# Dario_-_Rev_A2.net
KiCad netlist of a schematic drawn in EAGLE
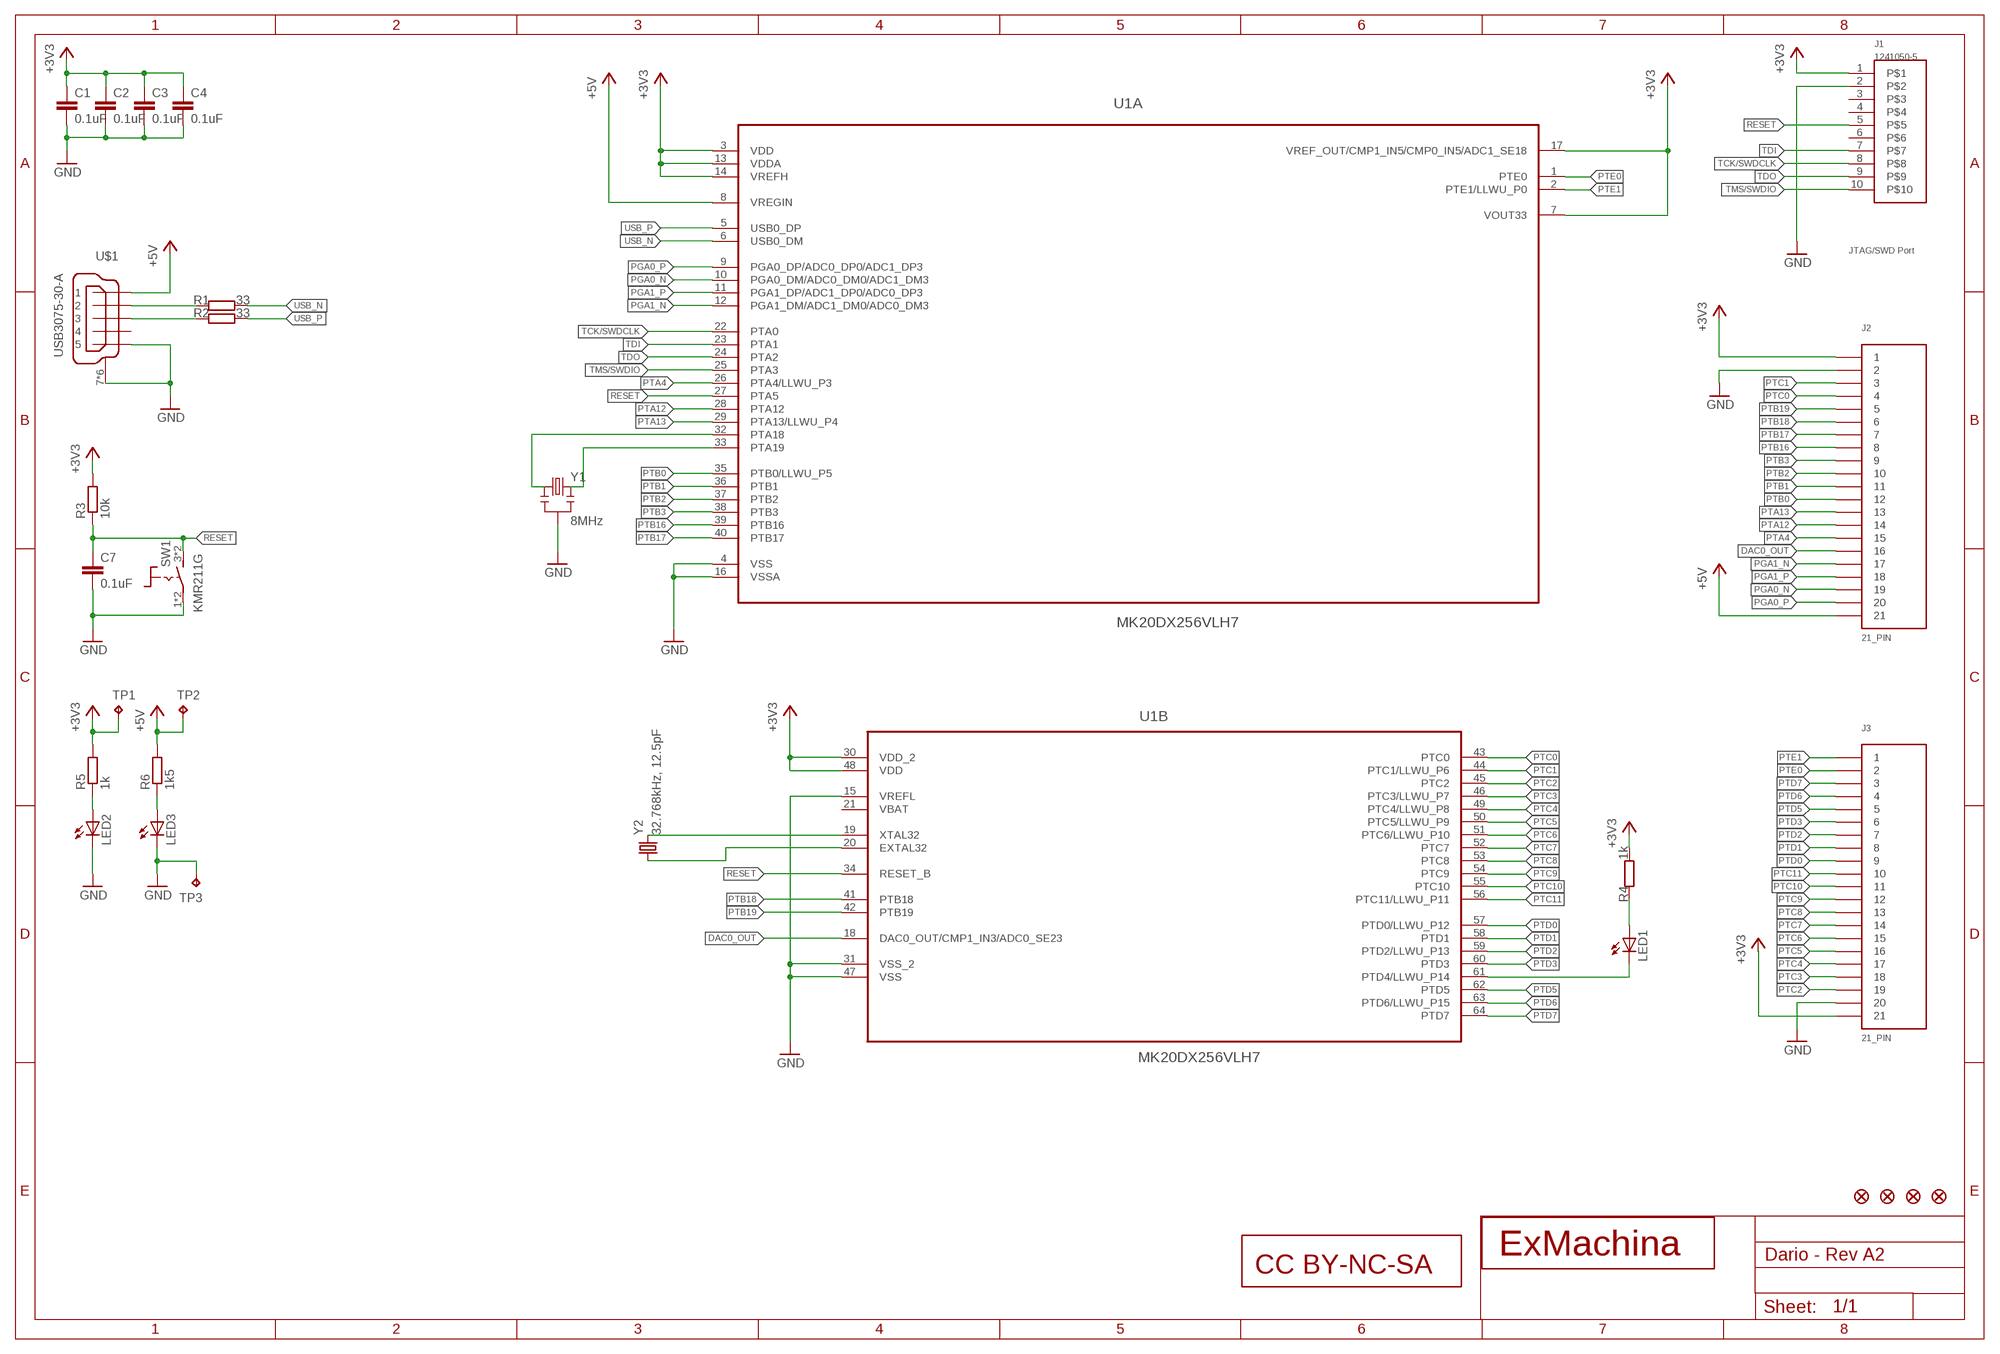
[diagram p0: schematic, sheet 1]

(export (version "E")
  (design (tool "Eeschema 10.0.6"))
  (components
    (comp (ref "C1")
      (value "0.1uF")
      (footprint "eagle-import:C0603")
      (fields (field (name "MPN") "MC0603B104K160CT"))
      (libsource (lib "eagle-import") (part "C-EUC0603"))
    )
    (comp (ref "C2")
      (value "0.1uF")
      (footprint "eagle-import:C0603")
      (fields (field (name "MPN") "MC0603B104K160CT"))
      (libsource (lib "eagle-import") (part "C-EUC0603"))
    )
    (comp (ref "C3")
      (value "0.1uF")
      (footprint "eagle-import:C0603")
      (fields (field (name "MPN") "MC0603B104K160CT"))
      (libsource (lib "eagle-import") (part "C-EUC0603"))
    )
    (comp (ref "C4")
      (value "0.1uF")
      (footprint "eagle-import:C0603")
      (fields (field (name "MPN") "MC0603B104K160CT"))
      (libsource (lib "eagle-import") (part "C-EUC0603"))
    )
    (comp (ref "C7")
      (value "0.1uF")
      (footprint "eagle-import:C0603")
      (fields (field (name "MPN") "MC0603B104K160CT"))
      (libsource (lib "eagle-import") (part "C-EUC0603"))
    )
    (comp (ref "J1")
      (value "1241050-5")
      (footprint "eagle-import:2.54_2X5")
      (libsource (lib "eagle-import") (part "1241050-5"))
    )
    (comp (ref "J2")
      (value "21_PIN")
      (footprint "eagle-import:21_CUSTOM")
      (libsource (lib "eagle-import") (part "21_PIN"))
    )
    (comp (ref "J3")
      (value "21_PIN")
      (footprint "eagle-import:21_CUSTOM")
      (libsource (lib "eagle-import") (part "21_PIN"))
    )
    (comp (ref "JP1")
      (value "FIDUCIAL1X2")
      (footprint "eagle-import:FIDUCIAL-1X2")
      (libsource (lib "eagle-import") (part "FIDUCIAL1X2"))
    )
    (comp (ref "JP2")
      (value "FIDUCIAL1X2")
      (footprint "eagle-import:FIDUCIAL-1X2")
      (libsource (lib "eagle-import") (part "FIDUCIAL1X2"))
    )
    (comp (ref "JP3")
      (value "FIDUCIAL1X2")
      (footprint "eagle-import:FIDUCIAL-1X2")
      (libsource (lib "eagle-import") (part "FIDUCIAL1X2"))
    )
    (comp (ref "JP4")
      (value "FIDUCIAL1X2")
      (footprint "eagle-import:FIDUCIAL-1X2")
      (libsource (lib "eagle-import") (part "FIDUCIAL1X2"))
    )
    (comp (ref "LED1")
      (value "LEDCHIP-LED0603")
      (footprint "eagle-import:CHIP-LED0603")
      (libsource (lib "eagle-import") (part "LEDCHIP-LED0603"))
    )
    (comp (ref "LED2")
      (value "LEDCHIP-LED0603")
      (footprint "eagle-import:CHIP-LED0603")
      (libsource (lib "eagle-import") (part "LEDCHIP-LED0603"))
    )
    (comp (ref "LED3")
      (value "LEDCHIP-LED0603")
      (footprint "eagle-import:CHIP-LED0603")
      (libsource (lib "eagle-import") (part "LEDCHIP-LED0603"))
    )
    (comp (ref "R1")
      (value "33")
      (footprint "eagle-import:R0603")
      (fields (field (name "MPN") "MCMR06X33R0FTL"))
      (libsource (lib "eagle-import") (part "R-EU_R0603"))
    )
    (comp (ref "R2")
      (value "33")
      (footprint "eagle-import:R0603")
      (fields (field (name "MPN") "MCMR06X33R0FTL"))
      (libsource (lib "eagle-import") (part "R-EU_R0603"))
    )
    (comp (ref "R3")
      (value "10k")
      (footprint "eagle-import:R0603")
      (fields (field (name "MPN") "MCMR06X1002FTL"))
      (libsource (lib "eagle-import") (part "R-EU_R0603"))
    )
    (comp (ref "R4")
      (value "1k")
      (footprint "eagle-import:R0603")
      (fields (field (name "MPN") "MCMR06X1001FTL"))
      (libsource (lib "eagle-import") (part "R-EU_R0603"))
    )
    (comp (ref "R5")
      (value "1k")
      (footprint "eagle-import:R0603")
      (fields (field (name "MPN") "MCMR06X1001FTL"))
      (libsource (lib "eagle-import") (part "R-EU_R0603"))
    )
    (comp (ref "R6")
      (value "1k5")
      (footprint "eagle-import:R0603")
      (fields (field (name "MPN") "MCMR06X1501FTL"))
      (libsource (lib "eagle-import") (part "R-EU_R0603"))
    )
    (comp (ref "SW1")
      (value "KMR211G")
      (footprint "eagle-import:KM_SERIE")
      (fields (field (name "MPN") "KMR211G LFS"))
      (libsource (lib "eagle-import") (part "KMR211G"))
    )
    (comp (ref "TP1")
      (value "TPB1,27")
      (footprint "eagle-import:B1,27")
      (libsource (lib "eagle-import") (part "TPB1,27"))
    )
    (comp (ref "TP2")
      (value "TPB1,27")
      (footprint "eagle-import:B1,27")
      (libsource (lib "eagle-import") (part "TPB1,27"))
    )
    (comp (ref "TP3")
      (value "TPB1,27")
      (footprint "eagle-import:B1,27")
      (libsource (lib "eagle-import") (part "TPB1,27"))
    )
    (comp (ref "U$1")
      (value "USB3075-30-A")
      (footprint "eagle-import:USB_MICROB_SMT")
      (libsource (lib "eagle-import") (part "USB3075-30-A"))
    )
    (comp (ref "U$3")
      (value "EXMACHINA-LOGO-NAME")
      (footprint "eagle-import:EXM-LOGO-BASELINE")
      (libsource (lib "eagle-import") (part "EXMACHINA-LOGO-NAME"))
    )
    (comp (ref "U$4")
      (value "CC-BY-NC-SA")
      (footprint "eagle-import:CC-BY-NC-SA")
      (libsource (lib "eagle-import") (part "CC-BY-NC-SA"))
    )
    (comp (ref "U1")
      (value "MK20DX256VLH7")
      (footprint "eagle-import:QFP50P1200X1200X160-64N")
      (libsource (lib "eagle-import") (part "MK20DX256VLH7"))
    )
    (comp (ref "Y1")
      (value "8MHz")
      (footprint "eagle-import:RESONATOR-SMD")
      (fields (field (name "MPN") "CSTCE8M00G55Z-R0"))
      (libsource (lib "eagle-import") (part "RESONATORSMD"))
    )
    (comp (ref "Y2")
      (value "32.768kHz, 12.5pF")
      (footprint "eagle-import:ABS07")
      (fields (field (name "MPN") "ABS07-32.768KHZ-1-T"))
      (libsource (lib "eagle-import") (part "ABS07-?32.768KHZ"))
    )
  )
  (nets
    (net (code "1") (name "+3V3") (class "Default")
      (node (ref "C1") (pin "1") (pinfunction "1_1") (pintype "passive"))
      (node (ref "C2") (pin "1") (pinfunction "1_1") (pintype "passive"))
      (node (ref "C3") (pin "1") (pinfunction "1_1") (pintype "passive"))
      (node (ref "C4") (pin "1") (pinfunction "1_1") (pintype "passive"))
      (node (ref "J1") (pin "1") (pinfunction "P$1_1") (pintype "bidirectional"))
      (node (ref "J2") (pin "P$1") (pinfunction "1_P$1") (pintype "bidirectional"))
      (node (ref "J3") (pin "P$21") (pinfunction "21_P$21") (pintype "bidirectional"))
      (node (ref "R3") (pin "2") (pinfunction "2_2") (pintype "passive"))
      (node (ref "R4") (pin "2") (pinfunction "2_2") (pintype "passive"))
      (node (ref "R5") (pin "2") (pinfunction "2_2") (pintype "passive"))
      (node (ref "TP1") (pin "TP") (pinfunction "TP_TP") (pintype "input"))
      (node (ref "U1") (pin "13") (pinfunction "VDDA_13") (pintype "power_in"))
      (node (ref "U1") (pin "14") (pinfunction "VREFH_14") (pintype "passive"))
      (node (ref "U1") (pin "17") (pinfunction "VREF_OUT/CMP1_IN5/CMP0_IN5/ADC1_SE18_17") (pintype "output"))
      (node (ref "U1") (pin "3") (pinfunction "VDD_3") (pintype "power_in"))
      (node (ref "U1") (pin "30") (pinfunction "VDD_2_30") (pintype "power_in"))
      (node (ref "U1") (pin "48") (pinfunction "VDD_48") (pintype "power_in"))
      (node (ref "U1") (pin "7") (pinfunction "VOUT33_7") (pintype "output"))
    )
    (net (code "2") (name "+5V") (class "Default")
      (node (ref "J2") (pin "P$21") (pinfunction "21_P$21") (pintype "bidirectional"))
      (node (ref "R6") (pin "2") (pinfunction "2_2") (pintype "passive"))
      (node (ref "TP2") (pin "TP") (pinfunction "TP_TP") (pintype "input"))
      (node (ref "U$1") (pin "1") (pinfunction "1_1") (pintype "passive"))
      (node (ref "U1") (pin "8") (pinfunction "VREGIN_8") (pintype "input"))
    )
    (net (code "3") (name "/VBAT") (class "Default")
      (node (ref "U1") (pin "21") (pinfunction "VBAT_21") (pintype "power_in"))
    )
    (net (code "4") (name "DAC0_OUT") (class "Default")
      (node (ref "J2") (pin "P$16") (pinfunction "16_P$16") (pintype "bidirectional"))
      (node (ref "U1") (pin "18") (pinfunction "DAC0_OUT/CMP1_IN3/ADC0_SE23_18") (pintype "passive"))
    )
    (net (code "5") (name "GND") (class "Default")
      (node (ref "C1") (pin "2") (pinfunction "2_2") (pintype "passive"))
      (node (ref "C2") (pin "2") (pinfunction "2_2") (pintype "passive"))
      (node (ref "C3") (pin "2") (pinfunction "2_2") (pintype "passive"))
      (node (ref "C4") (pin "2") (pinfunction "2_2") (pintype "passive"))
      (node (ref "C7") (pin "2") (pinfunction "2_2") (pintype "passive"))
      (node (ref "J1") (pin "2") (pinfunction "P$2_2") (pintype "bidirectional"))
      (node (ref "J2") (pin "P$2") (pinfunction "2_P$2") (pintype "bidirectional"))
      (node (ref "J3") (pin "P$20") (pinfunction "20_P$20") (pintype "bidirectional"))
      (node (ref "LED2") (pin "C") (pinfunction "C_C") (pintype "passive"))
      (node (ref "LED3") (pin "C") (pinfunction "C_C") (pintype "passive"))
      (node (ref "SW1") (pin "1") (pinfunction "2_1") (pintype "passive"))
      (node (ref "SW1") (pin "2") (pinfunction "2_2") (pintype "passive"))
      (node (ref "TP3") (pin "TP") (pinfunction "TP_TP") (pintype "input"))
      (node (ref "U$1") (pin "10") (pinfunction "S_10") (pintype "bidirectional"))
      (node (ref "U$1") (pin "11") (pinfunction "S_11") (pintype "bidirectional"))
      (node (ref "U$1") (pin "12") (pinfunction "S_12") (pintype "bidirectional"))
      (node (ref "U$1") (pin "5") (pinfunction "5_5") (pintype "passive"))
      (node (ref "U$1") (pin "7") (pinfunction "S_7") (pintype "bidirectional"))
      (node (ref "U$1") (pin "8") (pinfunction "S_8") (pintype "bidirectional"))
      (node (ref "U$1") (pin "9") (pinfunction "S_9") (pintype "bidirectional"))
      (node (ref "U1") (pin "15") (pinfunction "VREFL_15") (pintype "passive"))
      (node (ref "U1") (pin "16") (pinfunction "VSSA_16") (pintype "passive"))
      (node (ref "U1") (pin "31") (pinfunction "VSS_2_31") (pintype "passive"))
      (node (ref "U1") (pin "4") (pinfunction "VSS_4") (pintype "passive"))
      (node (ref "U1") (pin "47") (pinfunction "VSS_47") (pintype "passive"))
      (node (ref "Y1") (pin "2") (pinfunction "2_2") (pintype "passive"))
    )
    (net (code "6") (name "Net-(LED1-PadA)") (class "Default")
      (node (ref "LED1") (pin "A") (pinfunction "A_A") (pintype "passive"))
      (node (ref "R4") (pin "1") (pinfunction "1_1") (pintype "passive"))
    )
    (net (code "7") (name "Net-(LED2-PadA)") (class "Default")
      (node (ref "LED2") (pin "A") (pinfunction "A_A") (pintype "passive"))
      (node (ref "R5") (pin "1") (pinfunction "1_1") (pintype "passive"))
    )
    (net (code "8") (name "Net-(LED3-PadA)") (class "Default")
      (node (ref "LED3") (pin "A") (pinfunction "A_A") (pintype "passive"))
      (node (ref "R6") (pin "1") (pinfunction "1_1") (pintype "passive"))
    )
    (net (code "9") (name "Net-(R1-Pad1)") (class "Default")
      (node (ref "R1") (pin "1") (pinfunction "1_1") (pintype "passive"))
      (node (ref "U$1") (pin "2") (pinfunction "2_2") (pintype "passive"))
    )
    (net (code "10") (name "Net-(R2-Pad1)") (class "Default")
      (node (ref "R2") (pin "1") (pinfunction "1_1") (pintype "passive"))
      (node (ref "U$1") (pin "3") (pinfunction "3_3") (pintype "passive"))
    )
    (net (code "11") (name "Net-(U1A-PTA18)") (class "Default")
      (node (ref "U1") (pin "32") (pinfunction "PTA18_32") (pintype "bidirectional"))
      (node (ref "Y1") (pin "1") (pinfunction "1_1") (pintype "passive"))
    )
    (net (code "12") (name "Net-(U1A-PTA19)") (class "Default")
      (node (ref "U1") (pin "33") (pinfunction "PTA19_33") (pintype "bidirectional"))
      (node (ref "Y1") (pin "3") (pinfunction "3_3") (pintype "passive"))
    )
    (net (code "13") (name "Net-(U1B-EXTAL32)") (class "Default")
      (node (ref "U1") (pin "20") (pinfunction "EXTAL32_20") (pintype "passive"))
      (node (ref "Y2") (pin "1") (pinfunction "1_1") (pintype "passive"))
    )
    (net (code "14") (name "Net-(U1B-PTD4{slash}LLWU_P14)") (class "Default")
      (node (ref "LED1") (pin "C") (pinfunction "C_C") (pintype "passive"))
      (node (ref "U1") (pin "61") (pinfunction "PTD4/LLWU_P14_61") (pintype "bidirectional"))
    )
    (net (code "15") (name "Net-(U1B-XTAL32)") (class "Default")
      (node (ref "U1") (pin "19") (pinfunction "XTAL32_19") (pintype "passive"))
      (node (ref "Y2") (pin "2") (pinfunction "2_2") (pintype "passive"))
    )
    (net (code "16") (name "PGA0_N") (class "Default")
      (node (ref "J2") (pin "P$19") (pinfunction "19_P$19") (pintype "bidirectional"))
      (node (ref "U1") (pin "10") (pinfunction "PGA0_DM/ADC0_DM0/ADC1_DM3_10") (pintype "bidirectional"))
    )
    (net (code "17") (name "PGA0_P") (class "Default")
      (node (ref "J2") (pin "P$20") (pinfunction "20_P$20") (pintype "bidirectional"))
      (node (ref "U1") (pin "9") (pinfunction "PGA0_DP/ADC0_DP0/ADC1_DP3_9") (pintype "bidirectional"))
    )
    (net (code "18") (name "PGA1_N") (class "Default")
      (node (ref "J2") (pin "P$17") (pinfunction "17_P$17") (pintype "bidirectional"))
      (node (ref "U1") (pin "12") (pinfunction "PGA1_DM/ADC1_DM0/ADC0_DM3_12") (pintype "bidirectional"))
    )
    (net (code "19") (name "PGA1_P") (class "Default")
      (node (ref "J2") (pin "P$18") (pinfunction "18_P$18") (pintype "bidirectional"))
      (node (ref "U1") (pin "11") (pinfunction "PGA1_DP/ADC1_DP0/ADC0_DP3_11") (pintype "bidirectional"))
    )
    (net (code "20") (name "PTA4") (class "Default")
      (node (ref "J2") (pin "P$15") (pinfunction "15_P$15") (pintype "bidirectional"))
      (node (ref "U1") (pin "26") (pinfunction "PTA4/LLWU_P3_26") (pintype "bidirectional"))
    )
    (net (code "21") (name "PTA12") (class "Default")
      (node (ref "J2") (pin "P$14") (pinfunction "14_P$14") (pintype "bidirectional"))
      (node (ref "U1") (pin "28") (pinfunction "PTA12_28") (pintype "bidirectional"))
    )
    (net (code "22") (name "PTA13") (class "Default")
      (node (ref "J2") (pin "P$13") (pinfunction "13_P$13") (pintype "bidirectional"))
      (node (ref "U1") (pin "29") (pinfunction "PTA13/LLWU_P4_29") (pintype "bidirectional"))
    )
    (net (code "23") (name "PTB0") (class "Default")
      (node (ref "J2") (pin "P$12") (pinfunction "12_P$12") (pintype "bidirectional"))
      (node (ref "U1") (pin "35") (pinfunction "PTB0/LLWU_P5_35") (pintype "bidirectional"))
    )
    (net (code "24") (name "PTB1") (class "Default")
      (node (ref "J2") (pin "P$11") (pinfunction "11_P$11") (pintype "bidirectional"))
      (node (ref "U1") (pin "36") (pinfunction "PTB1_36") (pintype "bidirectional"))
    )
    (net (code "25") (name "PTB2") (class "Default")
      (node (ref "J2") (pin "P$10") (pinfunction "10_P$10") (pintype "bidirectional"))
      (node (ref "U1") (pin "37") (pinfunction "PTB2_37") (pintype "bidirectional"))
    )
    (net (code "26") (name "PTB3") (class "Default")
      (node (ref "J2") (pin "P$9") (pinfunction "9_P$9") (pintype "bidirectional"))
      (node (ref "U1") (pin "38") (pinfunction "PTB3_38") (pintype "bidirectional"))
    )
    (net (code "27") (name "PTB16") (class "Default")
      (node (ref "J2") (pin "P$8") (pinfunction "8_P$8") (pintype "bidirectional"))
      (node (ref "U1") (pin "39") (pinfunction "PTB16_39") (pintype "bidirectional"))
    )
    (net (code "28") (name "PTB17") (class "Default")
      (node (ref "J2") (pin "P$7") (pinfunction "7_P$7") (pintype "bidirectional"))
      (node (ref "U1") (pin "40") (pinfunction "PTB17_40") (pintype "bidirectional"))
    )
    (net (code "29") (name "PTB18") (class "Default")
      (node (ref "J2") (pin "P$6") (pinfunction "6_P$6") (pintype "bidirectional"))
      (node (ref "U1") (pin "41") (pinfunction "PTB18_41") (pintype "bidirectional"))
    )
    (net (code "30") (name "PTB19") (class "Default")
      (node (ref "J2") (pin "P$5") (pinfunction "5_P$5") (pintype "bidirectional"))
      (node (ref "U1") (pin "42") (pinfunction "PTB19_42") (pintype "bidirectional"))
    )
    (net (code "31") (name "PTC0") (class "Default")
      (node (ref "J2") (pin "P$4") (pinfunction "4_P$4") (pintype "bidirectional"))
      (node (ref "U1") (pin "43") (pinfunction "PTC0_43") (pintype "bidirectional"))
    )
    (net (code "32") (name "PTC1") (class "Default")
      (node (ref "J2") (pin "P$3") (pinfunction "3_P$3") (pintype "bidirectional"))
      (node (ref "U1") (pin "44") (pinfunction "PTC1/LLWU_P6_44") (pintype "bidirectional"))
    )
    (net (code "33") (name "PTC2") (class "Default")
      (node (ref "J3") (pin "P$19") (pinfunction "19_P$19") (pintype "bidirectional"))
      (node (ref "U1") (pin "45") (pinfunction "PTC2_45") (pintype "bidirectional"))
    )
    (net (code "34") (name "PTC3") (class "Default")
      (node (ref "J3") (pin "P$18") (pinfunction "18_P$18") (pintype "bidirectional"))
      (node (ref "U1") (pin "46") (pinfunction "PTC3/LLWU_P7_46") (pintype "bidirectional"))
    )
    (net (code "35") (name "PTC4") (class "Default")
      (node (ref "J3") (pin "P$17") (pinfunction "17_P$17") (pintype "bidirectional"))
      (node (ref "U1") (pin "49") (pinfunction "PTC4/LLWU_P8_49") (pintype "bidirectional"))
    )
    (net (code "36") (name "PTC5") (class "Default")
      (node (ref "J3") (pin "P$16") (pinfunction "16_P$16") (pintype "bidirectional"))
      (node (ref "U1") (pin "50") (pinfunction "PTC5/LLWU_P9_50") (pintype "bidirectional"))
    )
    (net (code "37") (name "PTC6") (class "Default")
      (node (ref "J3") (pin "P$15") (pinfunction "15_P$15") (pintype "bidirectional"))
      (node (ref "U1") (pin "51") (pinfunction "PTC6/LLWU_P10_51") (pintype "bidirectional"))
    )
    (net (code "38") (name "PTC7") (class "Default")
      (node (ref "J3") (pin "P$14") (pinfunction "14_P$14") (pintype "bidirectional"))
      (node (ref "U1") (pin "52") (pinfunction "PTC7_52") (pintype "bidirectional"))
    )
    (net (code "39") (name "PTC8") (class "Default")
      (node (ref "J3") (pin "P$13") (pinfunction "13_P$13") (pintype "bidirectional"))
      (node (ref "U1") (pin "53") (pinfunction "PTC8_53") (pintype "bidirectional"))
    )
    (net (code "40") (name "PTC9") (class "Default")
      (node (ref "J3") (pin "P$12") (pinfunction "12_P$12") (pintype "bidirectional"))
      (node (ref "U1") (pin "54") (pinfunction "PTC9_54") (pintype "bidirectional"))
    )
    (net (code "41") (name "PTC10") (class "Default")
      (node (ref "J3") (pin "P$11") (pinfunction "11_P$11") (pintype "bidirectional"))
      (node (ref "U1") (pin "55") (pinfunction "PTC10_55") (pintype "bidirectional"))
    )
    (net (code "42") (name "PTC11") (class "Default")
      (node (ref "J3") (pin "P$10") (pinfunction "10_P$10") (pintype "bidirectional"))
      (node (ref "U1") (pin "56") (pinfunction "PTC11/LLWU_P11_56") (pintype "bidirectional"))
    )
    (net (code "43") (name "PTD0") (class "Default")
      (node (ref "J3") (pin "P$9") (pinfunction "9_P$9") (pintype "bidirectional"))
      (node (ref "U1") (pin "57") (pinfunction "PTD0/LLWU_P12_57") (pintype "bidirectional"))
    )
    (net (code "44") (name "PTD1") (class "Default")
      (node (ref "J3") (pin "P$8") (pinfunction "8_P$8") (pintype "bidirectional"))
      (node (ref "U1") (pin "58") (pinfunction "PTD1_58") (pintype "bidirectional"))
    )
    (net (code "45") (name "PTD2") (class "Default")
      (node (ref "J3") (pin "P$7") (pinfunction "7_P$7") (pintype "bidirectional"))
      (node (ref "U1") (pin "59") (pinfunction "PTD2/LLWU_P13_59") (pintype "bidirectional"))
    )
    (net (code "46") (name "PTD3") (class "Default")
      (node (ref "J3") (pin "P$6") (pinfunction "6_P$6") (pintype "bidirectional"))
      (node (ref "U1") (pin "60") (pinfunction "PTD3_60") (pintype "bidirectional"))
    )
    (net (code "47") (name "PTD5") (class "Default")
      (node (ref "J3") (pin "P$5") (pinfunction "5_P$5") (pintype "bidirectional"))
      (node (ref "U1") (pin "62") (pinfunction "PTD5_62") (pintype "bidirectional"))
    )
    (net (code "48") (name "PTD6") (class "Default")
      (node (ref "J3") (pin "P$4") (pinfunction "4_P$4") (pintype "bidirectional"))
      (node (ref "U1") (pin "63") (pinfunction "PTD6/LLWU_P15_63") (pintype "bidirectional"))
    )
    (net (code "49") (name "PTD7") (class "Default")
      (node (ref "J3") (pin "P$3") (pinfunction "3_P$3") (pintype "bidirectional"))
      (node (ref "U1") (pin "64") (pinfunction "PTD7_64") (pintype "bidirectional"))
    )
    (net (code "50") (name "PTE0") (class "Default")
      (node (ref "J3") (pin "P$2") (pinfunction "2_P$2") (pintype "bidirectional"))
      (node (ref "U1") (pin "1") (pinfunction "PTE0_1") (pintype "bidirectional"))
    )
    (net (code "51") (name "PTE1") (class "Default")
      (node (ref "J3") (pin "P$1") (pinfunction "1_P$1") (pintype "bidirectional"))
      (node (ref "U1") (pin "2") (pinfunction "PTE1/LLWU_P0_2") (pintype "bidirectional"))
    )
    (net (code "52") (name "RESET") (class "Default")
      (node (ref "C7") (pin "1") (pinfunction "1_1") (pintype "passive"))
      (node (ref "J1") (pin "5") (pinfunction "P$5_5") (pintype "bidirectional"))
      (node (ref "R3") (pin "1") (pinfunction "1_1") (pintype "passive"))
      (node (ref "SW1") (pin "3") (pinfunction "1_3") (pintype "passive"))
      (node (ref "SW1") (pin "4") (pinfunction "1_4") (pintype "passive"))
      (node (ref "U1") (pin "27") (pinfunction "PTA5_27") (pintype "bidirectional"))
      (node (ref "U1") (pin "34") (pinfunction "RESET_B_34") (pintype "passive"))
    )
    (net (code "53") (name "TCK{slash}SWDCLK") (class "Default")
      (node (ref "J1") (pin "8") (pinfunction "P$8_8") (pintype "bidirectional"))
      (node (ref "U1") (pin "22") (pinfunction "PTA0_22") (pintype "bidirectional"))
    )
    (net (code "54") (name "TDI") (class "Default")
      (node (ref "J1") (pin "7") (pinfunction "P$7_7") (pintype "bidirectional"))
      (node (ref "U1") (pin "23") (pinfunction "PTA1_23") (pintype "bidirectional"))
    )
    (net (code "55") (name "TDO") (class "Default")
      (node (ref "J1") (pin "9") (pinfunction "P$9_9") (pintype "bidirectional"))
      (node (ref "U1") (pin "24") (pinfunction "PTA2_24") (pintype "bidirectional"))
    )
    (net (code "56") (name "TMS{slash}SWDIO") (class "Default")
      (node (ref "J1") (pin "10") (pinfunction "P$10_10") (pintype "bidirectional"))
      (node (ref "U1") (pin "25") (pinfunction "PTA3_25") (pintype "bidirectional"))
    )
    (net (code "57") (name "USB_N") (class "Default")
      (node (ref "R1") (pin "2") (pinfunction "2_2") (pintype "passive"))
      (node (ref "U1") (pin "6") (pinfunction "USB0_DM_6") (pintype "passive"))
    )
    (net (code "58") (name "USB_P") (class "Default")
      (node (ref "R2") (pin "2") (pinfunction "2_2") (pintype "passive"))
      (node (ref "U1") (pin "5") (pinfunction "USB0_DP_5") (pintype "passive"))
    )
    (net (code "59") (name "unconnected-(J1-P$3-Pad3)") (class "Default")
      (node (ref "J1") (pin "3") (pinfunction "P$3_3") (pintype "bidirectional"))
    )
    (net (code "60") (name "unconnected-(J1-P$4-Pad4)") (class "Default")
      (node (ref "J1") (pin "4") (pinfunction "P$4_4") (pintype "bidirectional"))
    )
    (net (code "61") (name "unconnected-(J1-P$6-Pad6)") (class "Default")
      (node (ref "J1") (pin "6") (pinfunction "P$6_6") (pintype "bidirectional"))
    )
    (net (code "62") (name "unconnected-(U$1-Pad4)") (class "Default")
      (node (ref "U$1") (pin "4") (pinfunction "4_4") (pintype "passive"))
    )
  )
)
